# CAN-to-CAN.net
KiCad netlist of a schematic drawn in Altium Designer
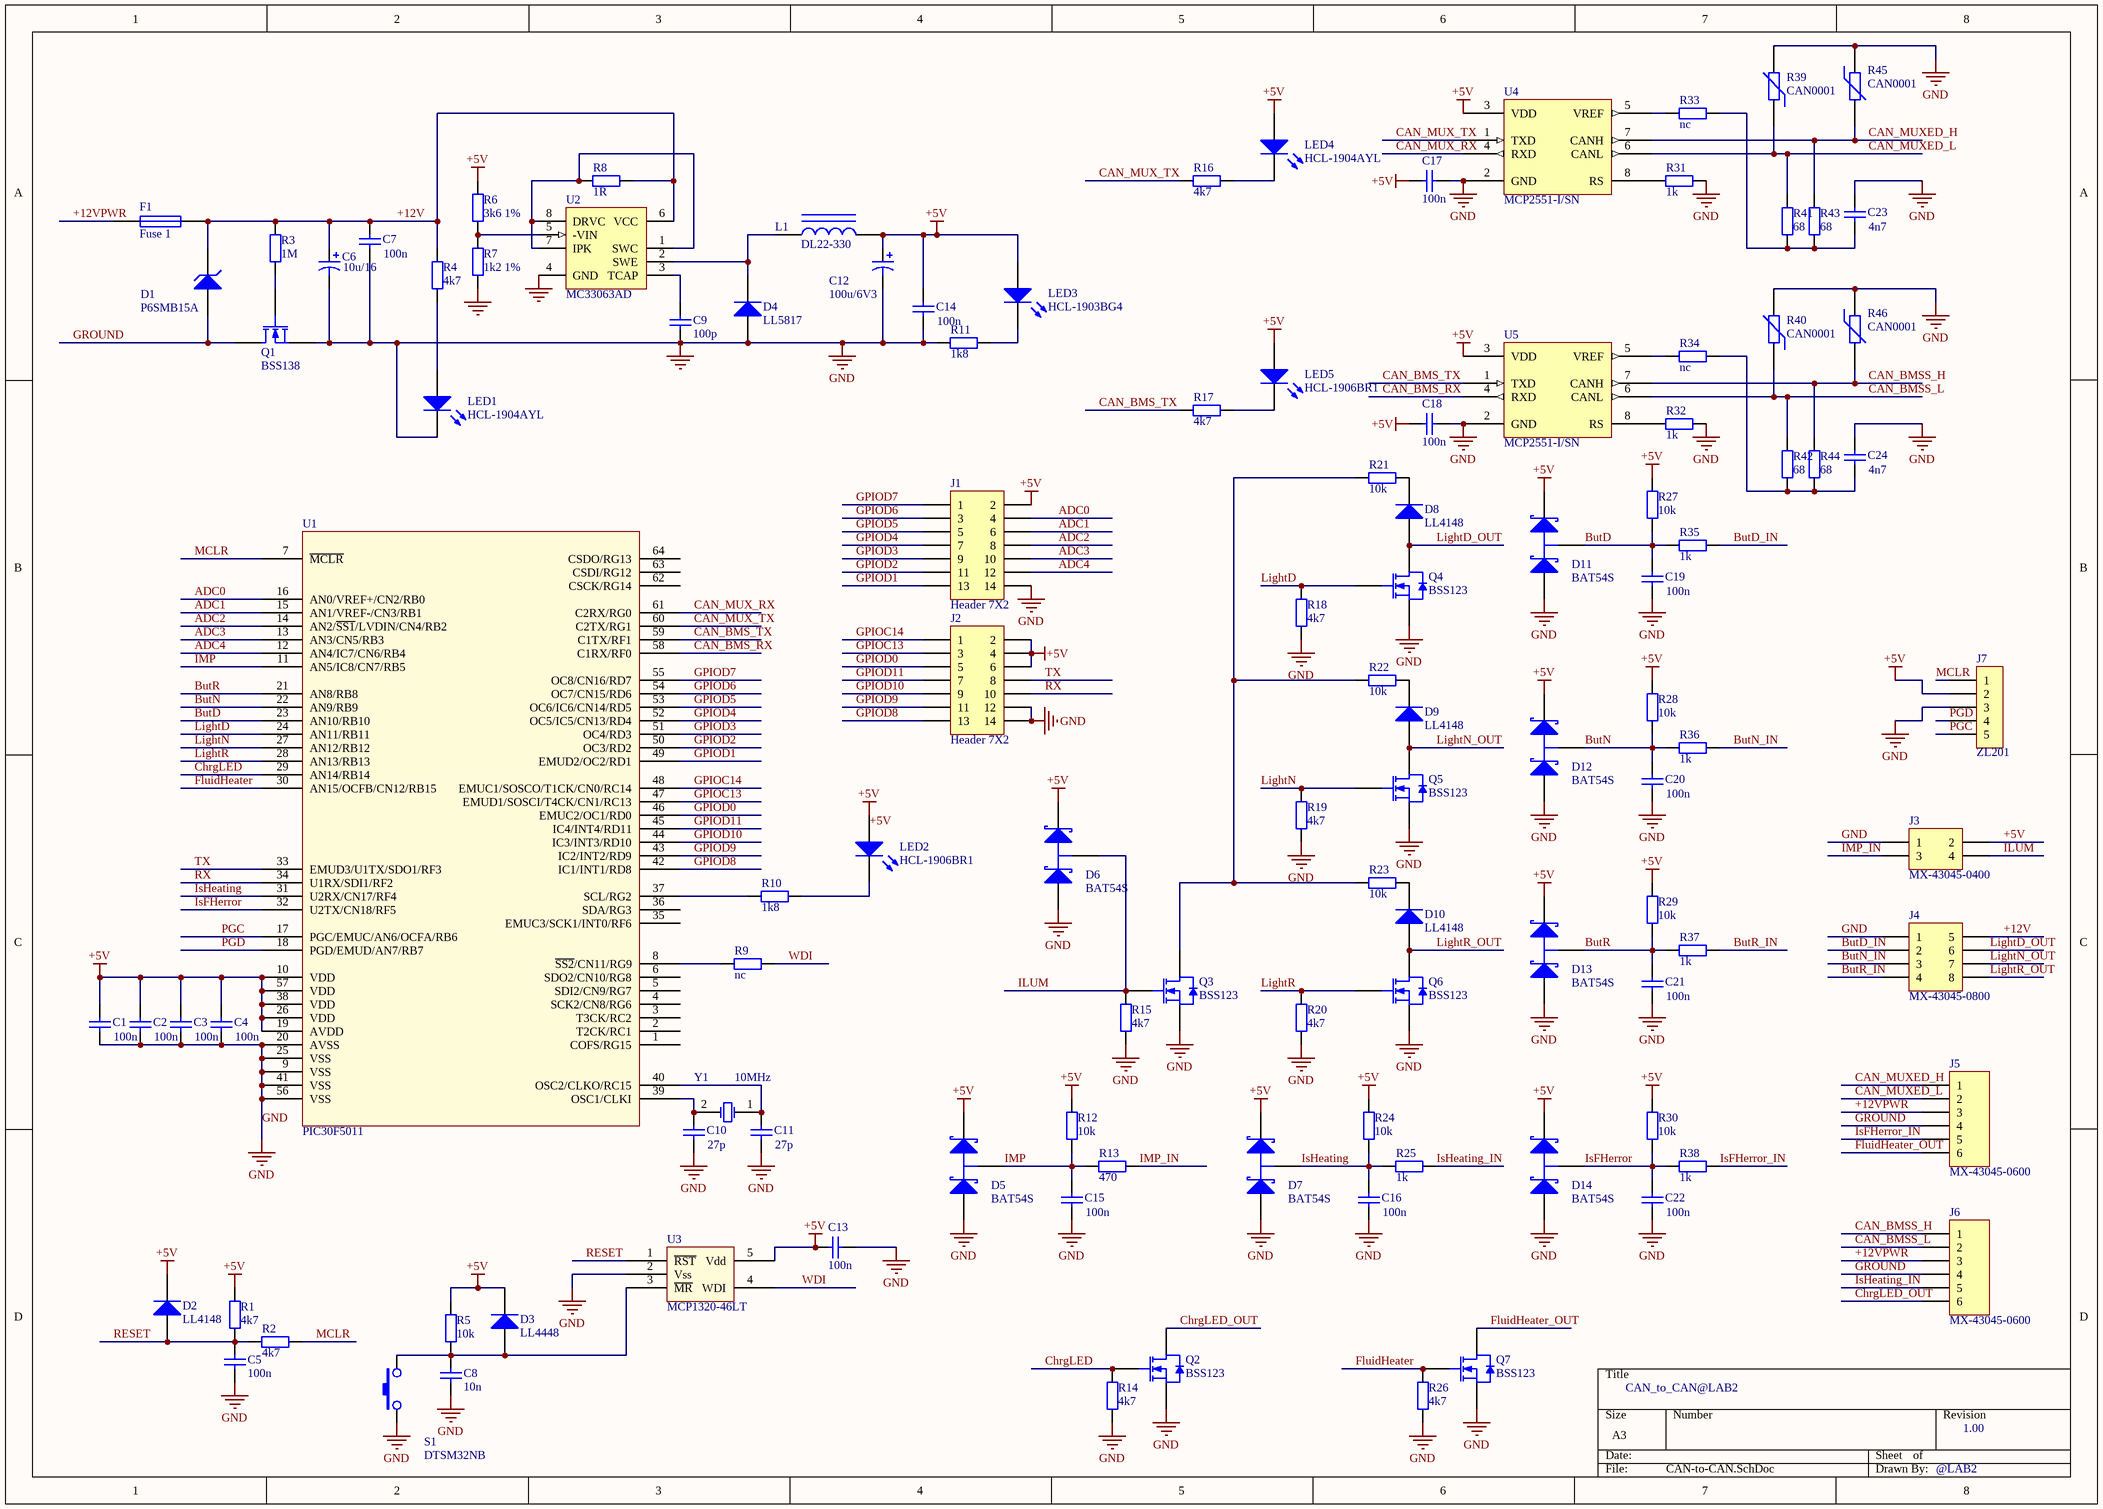
[diagram p0: CAN-to-CAN.SchDoc]

(export (version "E")
  (design (tool "Eeschema 10.0.6"))
  (components
    (comp (ref "C1")
      (value "100n")
      (footprint "0603")
      (description "Capacitor")
      (libsource (lib "Miscellaneous Devices") (part "Cap"))
    )
    (comp (ref "C2")
      (value "100n")
      (footprint "0603")
      (description "Capacitor")
      (libsource (lib "Miscellaneous Devices") (part "Cap"))
    )
    (comp (ref "C3")
      (value "100n")
      (footprint "0603")
      (description "Capacitor")
      (libsource (lib "Miscellaneous Devices") (part "Cap"))
    )
    (comp (ref "C4")
      (value "100n")
      (footprint "0603")
      (description "Capacitor")
      (libsource (lib "Miscellaneous Devices") (part "Cap"))
    )
    (comp (ref "C5")
      (value "100n")
      (footprint "0603")
      (description "Capacitor")
      (libsource (lib "Miscellaneous Devices") (part "Cap"))
    )
    (comp (ref "C6")
      (value "10u/16")
      (footprint "1608[0603]")
      (description "Polarized Capacitor (Radial)")
      (libsource (lib "Miscellaneous Devices") (part "Cap Pol1"))
    )
    (comp (ref "C7")
      (value "100n")
      (footprint "1812")
      (description "Capacitor")
      (libsource (lib "Miscellaneous Devices") (part "Cap"))
    )
    (comp (ref "C8")
      (value "10n")
      (footprint "0603")
      (description "Capacitor")
      (libsource (lib "Miscellaneous Devices") (part "Cap"))
    )
    (comp (ref "C9")
      (value "100p")
      (footprint "0603")
      (description "Capacitor")
      (libsource (lib "Miscellaneous Devices") (part "Cap"))
    )
    (comp (ref "C10")
      (value "27p")
      (footprint "0603")
      (description "Capacitor")
      (libsource (lib "Miscellaneous Devices") (part "Cap"))
    )
    (comp (ref "C11")
      (value "27p")
      (footprint "0603")
      (description "Capacitor")
      (libsource (lib "Miscellaneous Devices") (part "Cap"))
    )
    (comp (ref "C12")
      (value "100u/6V3")
      (footprint "0402")
      (description "Polarized Capacitor (Radial)")
      (libsource (lib "Miscellaneous Devices") (part "Cap Pol1"))
    )
    (comp (ref "C13")
      (value "100n")
      (footprint "0603")
      (description "Capacitor")
      (libsource (lib "Miscellaneous Devices") (part "Cap"))
    )
    (comp (ref "C14")
      (value "100n")
      (footprint "0603")
      (description "Capacitor")
      (libsource (lib "Miscellaneous Devices") (part "Cap"))
    )
    (comp (ref "C15")
      (value "100n")
      (footprint "0603")
      (description "Capacitor")
      (libsource (lib "Miscellaneous Devices") (part "Cap"))
    )
    (comp (ref "C16")
      (value "100n")
      (footprint "0603")
      (description "Capacitor")
      (libsource (lib "Miscellaneous Devices") (part "Cap"))
    )
    (comp (ref "C17")
      (value "100n")
      (footprint "0603")
      (description "Capacitor")
      (libsource (lib "Miscellaneous Devices") (part "Cap"))
    )
    (comp (ref "C18")
      (value "100n")
      (footprint "0603")
      (description "Capacitor")
      (libsource (lib "Miscellaneous Devices") (part "Cap"))
    )
    (comp (ref "C19")
      (value "100n")
      (footprint "0603")
      (description "Capacitor")
      (libsource (lib "Miscellaneous Devices") (part "Cap"))
    )
    (comp (ref "C20")
      (value "100n")
      (footprint "0603")
      (description "Capacitor")
      (libsource (lib "Miscellaneous Devices") (part "Cap"))
    )
    (comp (ref "C21")
      (value "100n")
      (footprint "0603")
      (description "Capacitor")
      (libsource (lib "Miscellaneous Devices") (part "Cap"))
    )
    (comp (ref "C22")
      (value "100n")
      (footprint "0603")
      (description "Capacitor")
      (libsource (lib "Miscellaneous Devices") (part "Cap"))
    )
    (comp (ref "C23")
      (value "4n7")
      (footprint "0603")
      (description "Capacitor")
      (libsource (lib "Miscellaneous Devices") (part "Cap"))
    )
    (comp (ref "C24")
      (value "4n7")
      (footprint "0603")
      (description "Capacitor")
      (libsource (lib "Miscellaneous Devices") (part "Cap"))
    )
    (comp (ref "D1")
      (value "P6SMB15A")
      (footprint "SMB")
      (description "Zener Diode")
      (libsource (lib "Miscellaneous Devices") (part "D Zener"))
    )
    (comp (ref "D2")
      (value "LL4148")
      (footprint "DIODE-0.4")
      (description "High Conductance Fast Diode")
      (libsource (lib "FSC Discrete Diode") (part "1N4148"))
    )
    (comp (ref "D3")
      (value "LL4448")
      (footprint "DIODE_SMC")
      (description "Default Diode")
      (libsource (lib "Miscellaneous Devices") (part "Diode"))
    )
    (comp (ref "D4")
      (value "LL5817")
      (footprint "DIODE-0.7")
      (description "High Conductance Fast Diode")
      (libsource (lib "FSC Discrete Diode") (part "1N4148"))
    )
    (comp (ref "D5")
      (value "BAT54S")
      (footprint "DO-35")
      (description "Schottky Barrier Double Diode")
      (libsource (lib "Philips Discrete Diode - Schottky") (part "BAT54S"))
    )
    (comp (ref "D6")
      (value "BAT54S")
      (footprint "DO-41")
      (description "Schottky Barrier Double Diode")
      (libsource (lib "Philips Discrete Diode - Schottky") (part "BAT54S"))
    )
    (comp (ref "D7")
      (value "BAT54S")
      (footprint "DO-204AL")
      (description "Schottky Barrier Double Diode")
      (libsource (lib "Philips Discrete Diode - Schottky") (part "BAT54S"))
    )
    (comp (ref "D8")
      (value "LL4148")
      (footprint "DO-201AD")
      (description "High Conductance Fast Diode")
      (libsource (lib "FSC Discrete Diode") (part "1N4148"))
    )
    (comp (ref "D9")
      (value "LL4148")
      (footprint "DIODE-0.4")
      (description "High Conductance Fast Diode")
      (libsource (lib "FSC Discrete Diode") (part "1N4148"))
    )
    (comp (ref "D10")
      (value "LL4148")
      (footprint "DO-7")
      (description "High Conductance Fast Diode")
      (libsource (lib "FSC Discrete Diode") (part "1N4148"))
    )
    (comp (ref "D11")
      (value "BAT54S")
      (footprint "DO-41")
      (description "Schottky Barrier Double Diode")
      (libsource (lib "Philips Discrete Diode - Schottky") (part "BAT54S"))
    )
    (comp (ref "D12")
      (value "BAT54S")
      (footprint "DO-201AD")
      (description "Schottky Barrier Double Diode")
      (libsource (lib "Philips Discrete Diode - Schottky") (part "BAT54S"))
    )
    (comp (ref "D13")
      (value "BAT54S")
      (footprint "DO-201AD")
      (description "Schottky Barrier Double Diode")
      (libsource (lib "Philips Discrete Diode - Schottky") (part "BAT54S"))
    )
    (comp (ref "D14")
      (value "BAT54S")
      (footprint "DO-41")
      (description "Schottky Barrier Double Diode")
      (libsource (lib "Philips Discrete Diode - Schottky") (part "BAT54S"))
    )
    (comp (ref "F1")
      (value "Fuse 1")
      (footprint "1812")
      (description "Fuse")
      (libsource (lib "Miscellaneous Devices") (part "Fuse 1"))
    )
    (comp (ref "J1")
      (value "Header 7X2")
      (footprint "HDR2X7")
      (description "Header, 7-Pin, Dual row")
      (libsource (lib "Miscellaneous Connectors") (part "Header 7X2"))
    )
    (comp (ref "J2")
      (value "Header 7X2")
      (footprint "HDR2X7")
      (description "Header, 7-Pin, Dual row")
      (libsource (lib "Miscellaneous Connectors") (part "Header 7X2"))
    )
    (comp (ref "J3")
      (value "MX-43045-0400")
      (footprint "SOT223_N")
      (description "Header, 2-Pin, Dual row")
      (libsource (lib "Miscellaneous Connectors") (part "Header 2X2"))
    )
    (comp (ref "J4")
      (value "MX-43045-0800")
      (footprint "DIP-8")
      (description "Header, 4-Pin, Dual row")
      (libsource (lib "Miscellaneous Connectors") (part "Header 4X2A"))
    )
    (comp (ref "J5")
      (value "MX-43045-0600")
      (footprint "DPDT-6")
      (description "Header, 6-Pin")
      (libsource (lib "Miscellaneous Connectors") (part "Header 6"))
    )
    (comp (ref "J6")
      (value "MX-43045-0600")
      (footprint "DPDT-6")
      (description "Header, 6-Pin")
      (libsource (lib "Miscellaneous Connectors") (part "Header 6"))
    )
    (comp (ref "J7")
      (value "ZL201")
      (footprint "HDR1X5")
      (description "Connector")
      (libsource (lib "*") (part "CON5"))
    )
    (comp (ref "L1")
      (value "DL22-330")
      (footprint "0603")
      (description "Magnetic-Core Inductor")
      (libsource (lib "Miscellaneous Devices") (part "Inductor Iron"))
    )
    (comp (ref "LED1")
      (value "HCL-1904AYL")
      (footprint "0603")
      (description "Typical BLUE SiC LED")
      (libsource (lib "Miscellaneous Devices") (part "LED3"))
    )
    (comp (ref "LED2")
      (value "HCL-1906BR1")
      (footprint "0603")
      (description "Typical BLUE SiC LED")
      (libsource (lib "Miscellaneous Devices") (part "LED3"))
    )
    (comp (ref "LED3")
      (value "HCL-1903BG4")
      (footprint "0603")
      (description "Typical BLUE SiC LED")
      (libsource (lib "Miscellaneous Devices") (part "LED3"))
    )
    (comp (ref "LED4")
      (value "HCL-1904AYL")
      (footprint "0603")
      (description "Typical BLUE SiC LED")
      (libsource (lib "Miscellaneous Devices") (part "LED3"))
    )
    (comp (ref "LED5")
      (value "HCL-1906BR1")
      (footprint "0603")
      (description "Typical BLUE SiC LED")
      (libsource (lib "Miscellaneous Devices") (part "LED3"))
    )
    (comp (ref "Q1")
      (value "BSS138")
      (footprint "SOT89L")
      (description "N-Channel Enhancement Mode Vertical DMOS FET")
      (libsource (lib "Zetex Discrete MOSFET") (part "BSS138"))
    )
    (comp (ref "Q2")
      (value "BSS123")
      (footprint "SOT23_M")
      (description "N-channel Enhancement Mode Vertical D-MOSFET")
      (libsource (lib "Philips Discrete MOSFET - Low Power") (part "BSS123"))
    )
    (comp (ref "Q3")
      (value "BSS123")
      (footprint "SOT23_M")
      (description "N-channel Enhancement Mode Vertical D-MOSFET")
      (libsource (lib "Philips Discrete MOSFET - Low Power") (part "BSS123"))
    )
    (comp (ref "Q4")
      (value "BSS123")
      (footprint "SOT89L")
      (description "N-channel Enhancement Mode Vertical D-MOSFET")
      (libsource (lib "Philips Discrete MOSFET - Low Power") (part "BSS123"))
    )
    (comp (ref "Q5")
      (value "BSS123")
      (footprint "DIP-P8")
      (description "N-channel Enhancement Mode Vertical D-MOSFET")
      (libsource (lib "Philips Discrete MOSFET - Low Power") (part "BSS123"))
    )
    (comp (ref "Q6")
      (value "BSS123")
      (footprint "DIODE_SMC")
      (description "N-channel Enhancement Mode Vertical D-MOSFET")
      (libsource (lib "Philips Discrete MOSFET - Low Power") (part "BSS123"))
    )
    (comp (ref "Q7")
      (value "BSS123")
      (footprint "SOT89N")
      (description "N-channel Enhancement Mode Vertical D-MOSFET")
      (libsource (lib "Philips Discrete MOSFET - Low Power") (part "BSS123"))
    )
    (comp (ref "R1")
      (value "4k7")
      (footprint "0603")
      (description "Resistor")
      (libsource (lib "") (part "Res2_2"))
    )
    (comp (ref "R2")
      (value "4k7")
      (footprint "0603")
      (description "Resistor")
      (libsource (lib "Miscellaneous Devices") (part "Res2"))
    )
    (comp (ref "R3")
      (value "1M")
      (footprint "6-0805_L")
      (description "Resistor")
      (libsource (lib "") (part "Res2_2"))
    )
    (comp (ref "R4")
      (value "4k7")
      (footprint "6-0805_N")
      (description "Resistor")
      (libsource (lib "") (part "Res2_2"))
    )
    (comp (ref "R5")
      (value "10k")
      (footprint "0603")
      (description "Resistor")
      (libsource (lib "") (part "Res2_3"))
    )
    (comp (ref "R6")
      (value "3k6 1%")
      (footprint "0603")
      (description "Resistor")
      (libsource (lib "") (part "Res2_2"))
    )
    (comp (ref "R7")
      (value "1k2 1%")
      (footprint "0603")
      (description "Resistor")
      (libsource (lib "") (part "Res2_3"))
    )
    (comp (ref "R8")
      (value "1R")
      (footprint "6-0805_L")
      (description "Resistor")
      (libsource (lib "") (part "Res2_1"))
    )
    (comp (ref "R9")
      (value "nc")
      (footprint "0603")
      (description "Resistor")
      (libsource (lib "Miscellaneous Devices") (part "Res2"))
    )
    (comp (ref "R10")
      (value "1k8")
      (footprint "0603")
      (description "Resistor")
      (libsource (lib "Miscellaneous Devices") (part "Res2"))
    )
    (comp (ref "R11")
      (value "1k8")
      (footprint "0603")
      (description "Resistor")
      (libsource (lib "Miscellaneous Devices") (part "Res2"))
    )
    (comp (ref "R12")
      (value "10k")
      (footprint "0603")
      (description "Resistor")
      (libsource (lib "") (part "Res2_2"))
    )
    (comp (ref "R13")
      (value "470")
      (footprint "0603")
      (description "Resistor")
      (libsource (lib "Miscellaneous Devices") (part "Res2"))
    )
    (comp (ref "R14")
      (value "4k7")
      (footprint "0603")
      (description "Resistor")
      (libsource (lib "") (part "Res2_2"))
    )
    (comp (ref "R15")
      (value "4k7")
      (footprint "0603")
      (description "Resistor")
      (libsource (lib "") (part "Res2_2"))
    )
    (comp (ref "R16")
      (value "4k7")
      (footprint "0603")
      (description "Resistor")
      (libsource (lib "Miscellaneous Devices") (part "Res2"))
    )
    (comp (ref "R17")
      (value "4k7")
      (footprint "0603")
      (description "Resistor")
      (libsource (lib "Miscellaneous Devices") (part "Res2"))
    )
    (comp (ref "R18")
      (value "4k7")
      (footprint "0603")
      (description "Resistor")
      (libsource (lib "") (part "Res2_2"))
    )
    (comp (ref "R19")
      (value "4k7")
      (footprint "0603")
      (description "Resistor")
      (libsource (lib "") (part "Res2_2"))
    )
    (comp (ref "R20")
      (value "4k7")
      (footprint "0603")
      (description "Resistor")
      (libsource (lib "") (part "Res2_2"))
    )
    (comp (ref "R21")
      (value "10k")
      (footprint "0603")
      (description "Resistor")
      (libsource (lib "") (part "Res2_1"))
    )
    (comp (ref "R22")
      (value "10k")
      (footprint "0603")
      (description "Resistor")
      (libsource (lib "") (part "Res2_1"))
    )
    (comp (ref "R23")
      (value "10k")
      (footprint "0603")
      (description "Resistor")
      (libsource (lib "") (part "Res2_1"))
    )
    (comp (ref "R24")
      (value "10k")
      (footprint "0603")
      (description "Resistor")
      (libsource (lib "") (part "Res2_2"))
    )
    (comp (ref "R25")
      (value "1k")
      (footprint "0603")
      (description "Resistor")
      (libsource (lib "Miscellaneous Devices") (part "Res2"))
    )
    (comp (ref "R26")
      (value "4k7")
      (footprint "0603")
      (description "Resistor")
      (libsource (lib "") (part "Res2_2"))
    )
    (comp (ref "R27")
      (value "10k")
      (footprint "0603")
      (description "Resistor")
      (libsource (lib "") (part "Res2_2"))
    )
    (comp (ref "R28")
      (value "10k")
      (footprint "0603")
      (description "Resistor")
      (libsource (lib "") (part "Res2_2"))
    )
    (comp (ref "R29")
      (value "10k")
      (footprint "0603")
      (description "Resistor")
      (libsource (lib "") (part "Res2_2"))
    )
    (comp (ref "R30")
      (value "10k")
      (footprint "0603")
      (description "Resistor")
      (libsource (lib "") (part "Res2_2"))
    )
    (comp (ref "R31")
      (value "1k")
      (footprint "0603")
      (description "Resistor")
      (libsource (lib "") (part "Res2_1"))
    )
    (comp (ref "R32")
      (value "1k")
      (footprint "0603")
      (description "Resistor")
      (libsource (lib "") (part "Res2_1"))
    )
    (comp (ref "R33")
      (value "nc")
      (footprint "0603")
      (description "Resistor")
      (libsource (lib "") (part "Res2_1"))
    )
    (comp (ref "R34")
      (value "nc")
      (footprint "0603")
      (description "Resistor")
      (libsource (lib "") (part "Res2_1"))
    )
    (comp (ref "R35")
      (value "1k")
      (footprint "0603")
      (description "Resistor")
      (libsource (lib "Miscellaneous Devices") (part "Res2"))
    )
    (comp (ref "R36")
      (value "1k")
      (footprint "0603")
      (description "Resistor")
      (libsource (lib "Miscellaneous Devices") (part "Res2"))
    )
    (comp (ref "R37")
      (value "1k")
      (footprint "0603")
      (description "Resistor")
      (libsource (lib "Miscellaneous Devices") (part "Res2"))
    )
    (comp (ref "R38")
      (value "1k")
      (footprint "0603")
      (description "Resistor")
      (libsource (lib "Miscellaneous Devices") (part "Res2"))
    )
    (comp (ref "R39")
      (value "CAN0001")
      (footprint "0603")
      (description "Varistor (Voltage-Sensitive Resistor)")
      (libsource (lib "Miscellaneous Devices") (part "Res Varistor"))
    )
    (comp (ref "R40")
      (value "CAN0001")
      (footprint "0603")
      (description "Varistor (Voltage-Sensitive Resistor)")
      (libsource (lib "Miscellaneous Devices") (part "Res Varistor"))
    )
    (comp (ref "R41")
      (value "68")
      (footprint "0603")
      (description "Resistor")
      (libsource (lib "") (part "Res2_2"))
    )
    (comp (ref "R42")
      (value "68")
      (footprint "0603")
      (description "Resistor")
      (libsource (lib "") (part "Res2_2"))
    )
    (comp (ref "R43")
      (value "68")
      (footprint "0603")
      (description "Resistor")
      (libsource (lib "") (part "Res2_2"))
    )
    (comp (ref "R44")
      (value "68")
      (footprint "0603")
      (description "Resistor")
      (libsource (lib "") (part "Res2_2"))
    )
    (comp (ref "R45")
      (value "CAN0001")
      (footprint "0603")
      (description "Varistor (Voltage-Sensitive Resistor)")
      (libsource (lib "Miscellaneous Devices") (part "Res Varistor"))
    )
    (comp (ref "R46")
      (value "CAN0001")
      (footprint "0603")
      (description "Varistor (Voltage-Sensitive Resistor)")
      (libsource (lib "Miscellaneous Devices") (part "Res Varistor"))
    )
    (comp (ref "S1")
      (value "DTSM32NB")
      (footprint "PIN-W2/E2.8")
      (description "Switch PushButton")
      (libsource (lib "*") (part "PUSHB"))
    )
    (comp (ref "U1")
      (value "PIC30F5011")
      (footprint "TQFP-64_L")
      (description "PIC30F5011 - Up")
      (libsource (lib "AD Microcontroller ARM") (part "PIC30F5011"))
    )
    (comp (ref "U2")
      (value "MC33063AD")
      (footprint "SO8_N")
      (description "DC-to-DC Converter Control Circuit")
      (libsource (lib "Motorola Power Mgt DC-DC Converter") (part "MC33063AD"))
    )
    (comp (ref "U3")
      (value "MCP1320-46LT")
      (footprint "MODULE5B")
      (libsource (lib "X-Tro's Misc") (part "MCP1320"))
    )
    (comp (ref "U4")
      (value "MCP2551-I/SN")
      (footprint "DB008_L")
      (description "High Speed CAN Transceiver, 8-Pin Plastic SOIC, Industrial Grade")
      (libsource (lib "Microchip Interface Line Transceiver") (part "MCP2551-I/SN"))
    )
    (comp (ref "U5")
      (value "MCP2551-I/SN")
      (footprint "DIP-8")
      (description "High Speed CAN Transceiver, 8-Pin Plastic SOIC, Industrial Grade")
      (libsource (lib "Microchip Interface Line Transceiver") (part "MCP2551-I/SN"))
    )
    (comp (ref "Y1")
      (value "10MHz")
      (footprint "SPST-2")
      (description "Crystal Oscillator")
      (libsource (lib "Miscellaneous Devices") (part "XTAL"))
    )
  )
  (nets
    (net (code "1") (name "+5V") (class "Default")
      (node (ref "C1") (pin "1") (pinfunction "1_1") (pintype "passive"))
      (node (ref "C12") (pin "1") (pinfunction "1_1") (pintype "passive"))
      (node (ref "C13") (pin "1") (pinfunction "1_1") (pintype "passive"))
      (node (ref "C14") (pin "1") (pinfunction "1_1") (pintype "passive"))
      (node (ref "C17") (pin "1") (pinfunction "1_1") (pintype "passive"))
      (node (ref "C18") (pin "1") (pinfunction "1_1") (pintype "passive"))
      (node (ref "C2") (pin "1") (pinfunction "1_1") (pintype "passive"))
      (node (ref "C3") (pin "1") (pinfunction "1_1") (pintype "passive"))
      (node (ref "C4") (pin "1") (pinfunction "1_1") (pintype "passive"))
      (node (ref "D11") (pin "2") (pinfunction "K_2") (pintype "passive"))
      (node (ref "D12") (pin "2") (pinfunction "K_2") (pintype "passive"))
      (node (ref "D13") (pin "2") (pinfunction "K_2") (pintype "passive"))
      (node (ref "D14") (pin "2") (pinfunction "K_2") (pintype "passive"))
      (node (ref "D2") (pin "2") (pinfunction "K_2") (pintype "passive"))
      (node (ref "D3") (pin "2") (pinfunction "K_2") (pintype "passive"))
      (node (ref "D5") (pin "2") (pinfunction "K_2") (pintype "passive"))
      (node (ref "D6") (pin "2") (pinfunction "K_2") (pintype "passive"))
      (node (ref "D7") (pin "2") (pinfunction "K_2") (pintype "passive"))
      (node (ref "J1") (pin "2") (pinfunction "2_2") (pintype "passive"))
      (node (ref "J2") (pin "2") (pinfunction "2_2") (pintype "passive"))
      (node (ref "J2") (pin "4") (pinfunction "4_4") (pintype "passive"))
      (node (ref "J2") (pin "6") (pinfunction "6_6") (pintype "passive"))
      (node (ref "J3") (pin "2") (pinfunction "2_2") (pintype "passive"))
      (node (ref "J7") (pin "2") (pinfunction "2_2") (pintype "passive"))
      (node (ref "L1") (pin "2") (pinfunction "2_2") (pintype "passive"))
      (node (ref "LED2") (pin "1") (pinfunction "A_1") (pintype "passive"))
      (node (ref "LED3") (pin "1") (pinfunction "A_1") (pintype "passive"))
      (node (ref "LED4") (pin "1") (pinfunction "A_1") (pintype "passive"))
      (node (ref "LED5") (pin "1") (pinfunction "A_1") (pintype "passive"))
      (node (ref "R1") (pin "1") (pinfunction "1_1") (pintype "passive"))
      (node (ref "R12") (pin "1") (pinfunction "1_1") (pintype "passive"))
      (node (ref "R24") (pin "1") (pinfunction "1_1") (pintype "passive"))
      (node (ref "R27") (pin "1") (pinfunction "1_1") (pintype "passive"))
      (node (ref "R28") (pin "1") (pinfunction "1_1") (pintype "passive"))
      (node (ref "R29") (pin "1") (pinfunction "1_1") (pintype "passive"))
      (node (ref "R30") (pin "1") (pinfunction "1_1") (pintype "passive"))
      (node (ref "R5") (pin "2") (pinfunction "2_2") (pintype "passive"))
      (node (ref "R6") (pin "1") (pinfunction "1_1") (pintype "passive"))
      (node (ref "U1") (pin "10") (pinfunction "VDD_10") (pintype "passive"))
      (node (ref "U1") (pin "19") (pinfunction "AVDD_19") (pintype "passive"))
      (node (ref "U1") (pin "26") (pinfunction "VDD_26") (pintype "passive"))
      (node (ref "U1") (pin "38") (pinfunction "VDD_38") (pintype "passive"))
      (node (ref "U1") (pin "57") (pinfunction "VDD_57") (pintype "passive"))
      (node (ref "U3") (pin "5") (pinfunction "Vdd_5") (pintype "passive"))
      (node (ref "U4") (pin "3") (pinfunction "VDD_3") (pintype "power_in"))
      (node (ref "U5") (pin "3") (pinfunction "VDD_3") (pintype "power_in"))
    )
    (net (code "2") (name "/+12V") (class "Default")
      (node (ref "C6") (pin "1") (pinfunction "1_1") (pintype "passive"))
      (node (ref "C7") (pin "1") (pinfunction "1_1") (pintype "passive"))
      (node (ref "D1") (pin "2") (pinfunction "K_2") (pintype "passive"))
      (node (ref "F1") (pin "2") (pinfunction "2_2") (pintype "passive"))
      (node (ref "J4") (pin "5") (pinfunction "5_5") (pintype "passive"))
      (node (ref "R3") (pin "1") (pinfunction "1_1") (pintype "passive"))
      (node (ref "R4") (pin "1") (pinfunction "1_1") (pintype "passive"))
      (node (ref "R8") (pin "2") (pinfunction "2_2") (pintype "passive"))
      (node (ref "U2") (pin "6") (pinfunction "VCC_6") (pintype "power_in"))
    )
    (net (code "3") (name "/+12VPWR") (class "Default")
      (node (ref "F1") (pin "1") (pinfunction "1_1") (pintype "passive"))
      (node (ref "J5") (pin "3") (pinfunction "3_3") (pintype "passive"))
      (node (ref "J6") (pin "3") (pinfunction "3_3") (pintype "passive"))
    )
    (net (code "4") (name "/ADC0") (class "Default")
      (node (ref "J1") (pin "4") (pinfunction "4_4") (pintype "passive"))
      (node (ref "U1") (pin "16") (pinfunction "AN0/VREF+/CN2/RB0_16") (pintype "passive"))
    )
    (net (code "5") (name "/ADC1") (class "Default")
      (node (ref "J1") (pin "6") (pinfunction "6_6") (pintype "passive"))
      (node (ref "U1") (pin "15") (pinfunction "AN1/VREF-/CN3/RB1_15") (pintype "passive"))
    )
    (net (code "6") (name "/ADC2") (class "Default")
      (node (ref "J1") (pin "8") (pinfunction "8_8") (pintype "passive"))
      (node (ref "U1") (pin "14") (pinfunction "AN2/~{SS1}/LVDIN/CN4/RB2_14") (pintype "passive"))
    )
    (net (code "7") (name "/ADC3") (class "Default")
      (node (ref "J1") (pin "10") (pinfunction "10_10") (pintype "passive"))
      (node (ref "U1") (pin "13") (pinfunction "AN3/CN5/RB3_13") (pintype "passive"))
    )
    (net (code "8") (name "/ADC4") (class "Default")
      (node (ref "J1") (pin "12") (pinfunction "12_12") (pintype "passive"))
      (node (ref "U1") (pin "12") (pinfunction "AN4/IC7/CN6/RB4_12") (pintype "passive"))
    )
    (net (code "9") (name "/ButD") (class "Default")
      (node (ref "C19") (pin "1") (pinfunction "1_1") (pintype "passive"))
      (node (ref "D11") (pin "3") (pinfunction "C_3") (pintype "passive"))
      (node (ref "R27") (pin "2") (pinfunction "2_2") (pintype "passive"))
      (node (ref "R35") (pin "2") (pinfunction "2_2") (pintype "passive"))
      (node (ref "U1") (pin "23") (pinfunction "AN10/RB10_23") (pintype "passive"))
    )
    (net (code "10") (name "/ButD_IN") (class "Default")
      (node (ref "J4") (pin "2") (pinfunction "2_2") (pintype "passive"))
      (node (ref "R35") (pin "1") (pinfunction "1_1") (pintype "passive"))
    )
    (net (code "11") (name "/ButN") (class "Default")
      (node (ref "C20") (pin "1") (pinfunction "1_1") (pintype "passive"))
      (node (ref "D12") (pin "3") (pinfunction "C_3") (pintype "passive"))
      (node (ref "R28") (pin "2") (pinfunction "2_2") (pintype "passive"))
      (node (ref "R36") (pin "2") (pinfunction "2_2") (pintype "passive"))
      (node (ref "U1") (pin "22") (pinfunction "AN9/RB9_22") (pintype "passive"))
    )
    (net (code "12") (name "/ButN_IN") (class "Default")
      (node (ref "J4") (pin "3") (pinfunction "3_3") (pintype "passive"))
      (node (ref "R36") (pin "1") (pinfunction "1_1") (pintype "passive"))
    )
    (net (code "13") (name "/ButR") (class "Default")
      (node (ref "C21") (pin "1") (pinfunction "1_1") (pintype "passive"))
      (node (ref "D13") (pin "3") (pinfunction "C_3") (pintype "passive"))
      (node (ref "R29") (pin "2") (pinfunction "2_2") (pintype "passive"))
      (node (ref "R37") (pin "2") (pinfunction "2_2") (pintype "passive"))
      (node (ref "U1") (pin "21") (pinfunction "AN8/RB8_21") (pintype "passive"))
    )
    (net (code "14") (name "/ButR_IN") (class "Default")
      (node (ref "J4") (pin "4") (pinfunction "4_4") (pintype "passive"))
      (node (ref "R37") (pin "1") (pinfunction "1_1") (pintype "passive"))
    )
    (net (code "15") (name "/CAN_BMSS_H") (class "Default")
      (node (ref "J6") (pin "1") (pinfunction "1_1") (pintype "passive"))
      (node (ref "R44") (pin "1") (pinfunction "1_1") (pintype "passive"))
      (node (ref "R46") (pin "2") (pinfunction "2_2") (pintype "passive"))
      (node (ref "U5") (pin "7") (pinfunction "CANH_7") (pintype "output"))
    )
    (net (code "16") (name "/CAN_BMSS_L") (class "Default")
      (node (ref "J6") (pin "2") (pinfunction "2_2") (pintype "passive"))
      (node (ref "R40") (pin "1") (pinfunction "1_1") (pintype "passive"))
      (node (ref "R42") (pin "1") (pinfunction "1_1") (pintype "passive"))
      (node (ref "U5") (pin "6") (pinfunction "CANL_6") (pintype "output"))
    )
    (net (code "17") (name "/CAN_BMS_RX") (class "Default")
      (node (ref "U1") (pin "58") (pinfunction "C1RX/RF0_58") (pintype "passive"))
      (node (ref "U5") (pin "4") (pinfunction "RXD_4") (pintype "output"))
    )
    (net (code "18") (name "/CAN_BMS_TX") (class "Default")
      (node (ref "R17") (pin "2") (pinfunction "2_2") (pintype "passive"))
      (node (ref "U1") (pin "59") (pinfunction "C1TX/RF1_59") (pintype "passive"))
      (node (ref "U5") (pin "1") (pinfunction "TXD_1") (pintype "input"))
    )
    (net (code "19") (name "/CAN_MUXED_H") (class "Default")
      (node (ref "J5") (pin "1") (pinfunction "1_1") (pintype "passive"))
      (node (ref "R43") (pin "1") (pinfunction "1_1") (pintype "passive"))
      (node (ref "R45") (pin "2") (pinfunction "2_2") (pintype "passive"))
      (node (ref "U4") (pin "7") (pinfunction "CANH_7") (pintype "output"))
    )
    (net (code "20") (name "/CAN_MUXED_L") (class "Default")
      (node (ref "J5") (pin "2") (pinfunction "2_2") (pintype "passive"))
      (node (ref "R39") (pin "1") (pinfunction "1_1") (pintype "passive"))
      (node (ref "R41") (pin "1") (pinfunction "1_1") (pintype "passive"))
      (node (ref "U4") (pin "6") (pinfunction "CANL_6") (pintype "output"))
    )
    (net (code "21") (name "/CAN_MUX_RX") (class "Default")
      (node (ref "U1") (pin "61") (pinfunction "C2RX/RG0_61") (pintype "passive"))
      (node (ref "U4") (pin "4") (pinfunction "RXD_4") (pintype "output"))
    )
    (net (code "22") (name "/CAN_MUX_TX") (class "Default")
      (node (ref "R16") (pin "2") (pinfunction "2_2") (pintype "passive"))
      (node (ref "U1") (pin "60") (pinfunction "C2TX/RG1_60") (pintype "passive"))
      (node (ref "U4") (pin "1") (pinfunction "TXD_1") (pintype "input"))
    )
    (net (code "23") (name "/ChrgLED") (class "Default")
      (node (ref "Q2") (pin "3") (pinfunction "G_3") (pintype "passive"))
      (node (ref "R14") (pin "1") (pinfunction "1_1") (pintype "passive"))
      (node (ref "U1") (pin "29") (pinfunction "AN14/RB14_29") (pintype "passive"))
    )
    (net (code "24") (name "/ChrgLED_OUT") (class "Default")
      (node (ref "J6") (pin "6") (pinfunction "6_6") (pintype "passive"))
      (node (ref "Q2") (pin "1") (pinfunction "D_1") (pintype "passive"))
    )
    (net (code "25") (name "/FluidHeater") (class "Default")
      (node (ref "Q7") (pin "3") (pinfunction "G_3") (pintype "passive"))
      (node (ref "R26") (pin "1") (pinfunction "1_1") (pintype "passive"))
      (node (ref "U1") (pin "30") (pinfunction "AN15/OCFB/CN12/RB15_30") (pintype "passive"))
    )
    (net (code "26") (name "/FluidHeater_OUT") (class "Default")
      (node (ref "J5") (pin "6") (pinfunction "6_6") (pintype "passive"))
      (node (ref "Q7") (pin "1") (pinfunction "D_1") (pintype "passive"))
    )
    (net (code "27") (name "/GPIOC13") (class "Default")
      (node (ref "J2") (pin "3") (pinfunction "3_3") (pintype "passive"))
      (node (ref "U1") (pin "47") (pinfunction "EMUD1/SOSCI/T4CK/CN1/RC13_47") (pintype "passive"))
    )
    (net (code "28") (name "/GPIOC14") (class "Default")
      (node (ref "J2") (pin "1") (pinfunction "1_1") (pintype "passive"))
      (node (ref "U1") (pin "48") (pinfunction "EMUC1/SOSCO/T1CK/CN0/RC14_48") (pintype "passive"))
    )
    (net (code "29") (name "/GPIOD0") (class "Default")
      (node (ref "J2") (pin "5") (pinfunction "5_5") (pintype "passive"))
      (node (ref "U1") (pin "46") (pinfunction "EMUC2/OC1/RD0_46") (pintype "passive"))
    )
    (net (code "30") (name "/GPIOD1") (class "Default")
      (node (ref "J1") (pin "13") (pinfunction "13_13") (pintype "passive"))
      (node (ref "U1") (pin "49") (pinfunction "EMUD2/OC2/RD1_49") (pintype "passive"))
    )
    (net (code "31") (name "/GPIOD2") (class "Default")
      (node (ref "J1") (pin "11") (pinfunction "11_11") (pintype "passive"))
      (node (ref "U1") (pin "50") (pinfunction "OC3/RD2_50") (pintype "passive"))
    )
    (net (code "32") (name "/GPIOD3") (class "Default")
      (node (ref "J1") (pin "9") (pinfunction "9_9") (pintype "passive"))
      (node (ref "U1") (pin "51") (pinfunction "OC4/RD3_51") (pintype "passive"))
    )
    (net (code "33") (name "/GPIOD4") (class "Default")
      (node (ref "J1") (pin "7") (pinfunction "7_7") (pintype "passive"))
      (node (ref "U1") (pin "52") (pinfunction "OC5/IC5/CN13/RD4_52") (pintype "passive"))
    )
    (net (code "34") (name "/GPIOD5") (class "Default")
      (node (ref "J1") (pin "5") (pinfunction "5_5") (pintype "passive"))
      (node (ref "U1") (pin "53") (pinfunction "OC6/IC6/CN14/RD5_53") (pintype "passive"))
    )
    (net (code "35") (name "/GPIOD6") (class "Default")
      (node (ref "J1") (pin "3") (pinfunction "3_3") (pintype "passive"))
      (node (ref "U1") (pin "54") (pinfunction "OC7/CN15/RD6_54") (pintype "passive"))
    )
    (net (code "36") (name "/GPIOD7") (class "Default")
      (node (ref "J1") (pin "1") (pinfunction "1_1") (pintype "passive"))
      (node (ref "U1") (pin "55") (pinfunction "OC8/CN16/RD7_55") (pintype "passive"))
    )
    (net (code "37") (name "/GPIOD8") (class "Default")
      (node (ref "J2") (pin "13") (pinfunction "13_13") (pintype "passive"))
      (node (ref "U1") (pin "42") (pinfunction "IC1/INT1/RD8_42") (pintype "passive"))
    )
    (net (code "38") (name "/GPIOD9") (class "Default")
      (node (ref "J2") (pin "11") (pinfunction "11_11") (pintype "passive"))
      (node (ref "U1") (pin "43") (pinfunction "IC2/INT2/RD9_43") (pintype "passive"))
    )
    (net (code "39") (name "/GPIOD10") (class "Default")
      (node (ref "J2") (pin "9") (pinfunction "9_9") (pintype "passive"))
      (node (ref "U1") (pin "44") (pinfunction "IC3/INT3/RD10_44") (pintype "passive"))
    )
    (net (code "40") (name "/GPIOD11") (class "Default")
      (node (ref "J2") (pin "7") (pinfunction "7_7") (pintype "passive"))
      (node (ref "U1") (pin "45") (pinfunction "IC4/INT4/RD11_45") (pintype "passive"))
    )
    (net (code "41") (name "/GROUND") (class "Default")
      (node (ref "D1") (pin "1") (pinfunction "A_1") (pintype "passive"))
      (node (ref "J5") (pin "4") (pinfunction "4_4") (pintype "passive"))
      (node (ref "J6") (pin "4") (pinfunction "4_4") (pintype "passive"))
      (node (ref "Q1") (pin "1") (pinfunction "D_1") (pintype "passive"))
    )
    (net (code "42") (name "/ILUM") (class "Default")
      (node (ref "D6") (pin "3") (pinfunction "C_3") (pintype "passive"))
      (node (ref "J3") (pin "4") (pinfunction "4_4") (pintype "passive"))
      (node (ref "Q3") (pin "3") (pinfunction "G_3") (pintype "passive"))
      (node (ref "R15") (pin "1") (pinfunction "1_1") (pintype "passive"))
    )
    (net (code "43") (name "/IMP") (class "Default")
      (node (ref "C15") (pin "1") (pinfunction "1_1") (pintype "passive"))
      (node (ref "D5") (pin "3") (pinfunction "C_3") (pintype "passive"))
      (node (ref "R12") (pin "2") (pinfunction "2_2") (pintype "passive"))
      (node (ref "R13") (pin "2") (pinfunction "2_2") (pintype "passive"))
      (node (ref "U1") (pin "11") (pinfunction "AN5/IC8/CN7/RB5_11") (pintype "passive"))
    )
    (net (code "44") (name "/IMP_IN") (class "Default")
      (node (ref "J3") (pin "3") (pinfunction "3_3") (pintype "passive"))
      (node (ref "R13") (pin "1") (pinfunction "1_1") (pintype "passive"))
    )
    (net (code "45") (name "/IsFHerror") (class "Default")
      (node (ref "C22") (pin "1") (pinfunction "1_1") (pintype "passive"))
      (node (ref "D14") (pin "3") (pinfunction "C_3") (pintype "passive"))
      (node (ref "R30") (pin "2") (pinfunction "2_2") (pintype "passive"))
      (node (ref "R38") (pin "2") (pinfunction "2_2") (pintype "passive"))
      (node (ref "U1") (pin "32") (pinfunction "U2TX/CN18/RF5_32") (pintype "passive"))
    )
    (net (code "46") (name "/IsFHerror_IN") (class "Default")
      (node (ref "J5") (pin "5") (pinfunction "5_5") (pintype "passive"))
      (node (ref "R38") (pin "1") (pinfunction "1_1") (pintype "passive"))
    )
    (net (code "47") (name "/IsHeating") (class "Default")
      (node (ref "C16") (pin "1") (pinfunction "1_1") (pintype "passive"))
      (node (ref "D7") (pin "3") (pinfunction "C_3") (pintype "passive"))
      (node (ref "R24") (pin "2") (pinfunction "2_2") (pintype "passive"))
      (node (ref "R25") (pin "2") (pinfunction "2_2") (pintype "passive"))
      (node (ref "U1") (pin "31") (pinfunction "U2RX/CN17/RF4_31") (pintype "passive"))
    )
    (net (code "48") (name "/IsHeating_IN") (class "Default")
      (node (ref "J6") (pin "5") (pinfunction "5_5") (pintype "passive"))
      (node (ref "R25") (pin "1") (pinfunction "1_1") (pintype "passive"))
    )
    (net (code "49") (name "/LightD") (class "Default")
      (node (ref "Q4") (pin "3") (pinfunction "G_3") (pintype "passive"))
      (node (ref "R18") (pin "1") (pinfunction "1_1") (pintype "passive"))
      (node (ref "U1") (pin "24") (pinfunction "AN11/RB11_24") (pintype "passive"))
    )
    (net (code "50") (name "/LightD_OUT") (class "Default")
      (node (ref "D8") (pin "1") (pinfunction "A_1") (pintype "passive"))
      (node (ref "J4") (pin "6") (pinfunction "6_6") (pintype "passive"))
      (node (ref "Q4") (pin "1") (pinfunction "D_1") (pintype "passive"))
    )
    (net (code "51") (name "/LightN") (class "Default")
      (node (ref "Q5") (pin "3") (pinfunction "G_3") (pintype "passive"))
      (node (ref "R19") (pin "1") (pinfunction "1_1") (pintype "passive"))
      (node (ref "U1") (pin "27") (pinfunction "AN12/RB12_27") (pintype "passive"))
    )
    (net (code "52") (name "/LightN_OUT") (class "Default")
      (node (ref "D9") (pin "1") (pinfunction "A_1") (pintype "passive"))
      (node (ref "J4") (pin "7") (pinfunction "7_7") (pintype "passive"))
      (node (ref "Q5") (pin "1") (pinfunction "D_1") (pintype "passive"))
    )
    (net (code "53") (name "/LightR") (class "Default")
      (node (ref "Q6") (pin "3") (pinfunction "G_3") (pintype "passive"))
      (node (ref "R20") (pin "1") (pinfunction "1_1") (pintype "passive"))
      (node (ref "U1") (pin "28") (pinfunction "AN13/RB13_28") (pintype "passive"))
    )
    (net (code "54") (name "/LightR_OUT") (class "Default")
      (node (ref "D10") (pin "1") (pinfunction "A_1") (pintype "passive"))
      (node (ref "J4") (pin "8") (pinfunction "8_8") (pintype "passive"))
      (node (ref "Q6") (pin "1") (pinfunction "D_1") (pintype "passive"))
    )
    (net (code "55") (name "/MCLR") (class "Default")
      (node (ref "J7") (pin "1") (pinfunction "1_1") (pintype "passive"))
      (node (ref "R2") (pin "1") (pinfunction "1_1") (pintype "passive"))
      (node (ref "U1") (pin "7") (pinfunction "~{MCLR}_7") (pintype "passive"))
    )
    (net (code "56") (name "/PGC") (class "Default")
      (node (ref "J7") (pin "5") (pinfunction "5_5") (pintype "passive"))
      (node (ref "U1") (pin "17") (pinfunction "PGC/EMUC/AN6/OCFA/RB6_17") (pintype "passive"))
    )
    (net (code "57") (name "/PGD") (class "Default")
      (node (ref "J7") (pin "4") (pinfunction "4_4") (pintype "passive"))
      (node (ref "U1") (pin "18") (pinfunction "PGD/EMUD/AN7/RB7_18") (pintype "passive"))
    )
    (net (code "58") (name "/RESET") (class "Default")
      (node (ref "C5") (pin "2") (pinfunction "2_2") (pintype "passive"))
      (node (ref "D2") (pin "1") (pinfunction "A_1") (pintype "passive"))
      (node (ref "R1") (pin "2") (pinfunction "2_2") (pintype "passive"))
      (node (ref "R2") (pin "2") (pinfunction "2_2") (pintype "passive"))
      (node (ref "U3") (pin "1") (pinfunction "~{RST}_1") (pintype "passive"))
    )
    (net (code "59") (name "/RX") (class "Default")
      (node (ref "J2") (pin "10") (pinfunction "10_10") (pintype "passive"))
      (node (ref "U1") (pin "34") (pinfunction "U1RX/SDI1/RF2_34") (pintype "passive"))
    )
    (net (code "60") (name "/TX") (class "Default")
      (node (ref "J2") (pin "8") (pinfunction "8_8") (pintype "passive"))
      (node (ref "U1") (pin "33") (pinfunction "EMUD3/U1TX/SDO1/RF3_33") (pintype "passive"))
    )
    (net (code "61") (name "/WDI") (class "Default")
      (node (ref "R9") (pin "1") (pinfunction "1_1") (pintype "passive"))
      (node (ref "U3") (pin "4") (pinfunction "WDI_4") (pintype "passive"))
    )
    (net (code "62") (name "GND") (class "Default")
      (node (ref "C1") (pin "2") (pinfunction "2_2") (pintype "passive"))
      (node (ref "C10") (pin "2") (pinfunction "2_2") (pintype "passive"))
      (node (ref "C11") (pin "2") (pinfunction "2_2") (pintype "passive"))
      (node (ref "C12") (pin "2") (pinfunction "2_2") (pintype "passive"))
      (node (ref "C13") (pin "2") (pinfunction "2_2") (pintype "passive"))
      (node (ref "C14") (pin "2") (pinfunction "2_2") (pintype "passive"))
      (node (ref "C15") (pin "2") (pinfunction "2_2") (pintype "passive"))
      (node (ref "C16") (pin "2") (pinfunction "2_2") (pintype "passive"))
      (node (ref "C17") (pin "2") (pinfunction "2_2") (pintype "passive"))
      (node (ref "C18") (pin "2") (pinfunction "2_2") (pintype "passive"))
      (node (ref "C19") (pin "2") (pinfunction "2_2") (pintype "passive"))
      (node (ref "C2") (pin "2") (pinfunction "2_2") (pintype "passive"))
      (node (ref "C20") (pin "2") (pinfunction "2_2") (pintype "passive"))
      (node (ref "C21") (pin "2") (pinfunction "2_2") (pintype "passive"))
      (node (ref "C22") (pin "2") (pinfunction "2_2") (pintype "passive"))
      (node (ref "C23") (pin "1") (pinfunction "1_1") (pintype "passive"))
      (node (ref "C24") (pin "1") (pinfunction "1_1") (pintype "passive"))
      (node (ref "C3") (pin "2") (pinfunction "2_2") (pintype "passive"))
      (node (ref "C4") (pin "2") (pinfunction "2_2") (pintype "passive"))
      (node (ref "C5") (pin "1") (pinfunction "1_1") (pintype "passive"))
      (node (ref "C6") (pin "2") (pinfunction "2_2") (pintype "passive"))
      (node (ref "C7") (pin "2") (pinfunction "2_2") (pintype "passive"))
      (node (ref "C8") (pin "1") (pinfunction "1_1") (pintype "passive"))
      (node (ref "C9") (pin "1") (pinfunction "1_1") (pintype "passive"))
      (node (ref "D11") (pin "1") (pinfunction "A_1") (pintype "passive"))
      (node (ref "D12") (pin "1") (pinfunction "A_1") (pintype "passive"))
      (node (ref "D13") (pin "1") (pinfunction "A_1") (pintype "passive"))
      (node (ref "D14") (pin "1") (pinfunction "A_1") (pintype "passive"))
      (node (ref "D4") (pin "1") (pinfunction "A_1") (pintype "passive"))
      (node (ref "D5") (pin "1") (pinfunction "A_1") (pintype "passive"))
      (node (ref "D6") (pin "1") (pinfunction "A_1") (pintype "passive"))
      (node (ref "D7") (pin "1") (pinfunction "A_1") (pintype "passive"))
      (node (ref "J1") (pin "14") (pinfunction "14_14") (pintype "passive"))
      (node (ref "J2") (pin "12") (pinfunction "12_12") (pintype "passive"))
      (node (ref "J2") (pin "14") (pinfunction "14_14") (pintype "passive"))
      (node (ref "J3") (pin "1") (pinfunction "1_1") (pintype "passive"))
      (node (ref "J4") (pin "1") (pinfunction "1_1") (pintype "passive"))
      (node (ref "J7") (pin "3") (pinfunction "3_3") (pintype "passive"))
      (node (ref "LED1") (pin "2") (pinfunction "K_2") (pintype "passive"))
      (node (ref "Q1") (pin "2") (pinfunction "S_2") (pintype "passive"))
      (node (ref "Q2") (pin "2") (pinfunction "S_2") (pintype "passive"))
      (node (ref "Q3") (pin "2") (pinfunction "S_2") (pintype "passive"))
      (node (ref "Q4") (pin "2") (pinfunction "S_2") (pintype "passive"))
      (node (ref "Q5") (pin "2") (pinfunction "S_2") (pintype "passive"))
      (node (ref "Q6") (pin "2") (pinfunction "S_2") (pintype "passive"))
      (node (ref "Q7") (pin "2") (pinfunction "S_2") (pintype "passive"))
      (node (ref "R11") (pin "2") (pinfunction "2_2") (pintype "passive"))
      (node (ref "R14") (pin "2") (pinfunction "2_2") (pintype "passive"))
      (node (ref "R15") (pin "2") (pinfunction "2_2") (pintype "passive"))
      (node (ref "R18") (pin "2") (pinfunction "2_2") (pintype "passive"))
      (node (ref "R19") (pin "2") (pinfunction "2_2") (pintype "passive"))
      (node (ref "R20") (pin "2") (pinfunction "2_2") (pintype "passive"))
      (node (ref "R26") (pin "2") (pinfunction "2_2") (pintype "passive"))
      (node (ref "R31") (pin "2") (pinfunction "2_2") (pintype "passive"))
      (node (ref "R32") (pin "2") (pinfunction "2_2") (pintype "passive"))
      (node (ref "R39") (pin "2") (pinfunction "2_2") (pintype "passive"))
      (node (ref "R40") (pin "2") (pinfunction "2_2") (pintype "passive"))
      (node (ref "R45") (pin "1") (pinfunction "1_1") (pintype "passive"))
      (node (ref "R46") (pin "1") (pinfunction "1_1") (pintype "passive"))
      (node (ref "R7") (pin "1") (pinfunction "1_1") (pintype "passive"))
      (node (ref "S1") (pin "1") (pintype "passive"))
      (node (ref "U1") (pin "20") (pinfunction "AVSS_20") (pintype "passive"))
      (node (ref "U1") (pin "25") (pinfunction "VSS_25") (pintype "passive"))
      (node (ref "U1") (pin "41") (pinfunction "VSS_41") (pintype "passive"))
      (node (ref "U1") (pin "56") (pinfunction "VSS_56") (pintype "passive"))
      (node (ref "U1") (pin "9") (pinfunction "VSS_9") (pintype "passive"))
      (node (ref "U2") (pin "4") (pinfunction "GND_4") (pintype "power_in"))
      (node (ref "U3") (pin "2") (pinfunction "Vss_2") (pintype "passive"))
      (node (ref "U4") (pin "2") (pinfunction "GND_2") (pintype "power_in"))
      (node (ref "U5") (pin "2") (pinfunction "GND_2") (pintype "power_in"))
    )
    (net (code "63") (name "Net-(C23-Pad2)") (class "Default")
      (node (ref "C23") (pin "2") (pinfunction "2_2") (pintype "passive"))
      (node (ref "R33") (pin "2") (pinfunction "2_2") (pintype "passive"))
      (node (ref "R41") (pin "2") (pinfunction "2_2") (pintype "passive"))
      (node (ref "R43") (pin "2") (pinfunction "2_2") (pintype "passive"))
    )
    (net (code "64") (name "Net-(C24-Pad2)") (class "Default")
      (node (ref "C24") (pin "2") (pinfunction "2_2") (pintype "passive"))
      (node (ref "R34") (pin "2") (pinfunction "2_2") (pintype "passive"))
      (node (ref "R42") (pin "2") (pinfunction "2_2") (pintype "passive"))
      (node (ref "R44") (pin "2") (pinfunction "2_2") (pintype "passive"))
    )
    (net (code "65") (name "Net-(D3-A)") (class "Default")
      (node (ref "C8") (pin "2") (pinfunction "2_2") (pintype "passive"))
      (node (ref "D3") (pin "1") (pinfunction "A_1") (pintype "passive"))
      (node (ref "R5") (pin "1") (pinfunction "1_1") (pintype "passive"))
      (node (ref "S1") (pin "2") (pintype "passive"))
      (node (ref "U3") (pin "3") (pinfunction "~{MR}_3") (pintype "passive"))
    )
    (net (code "66") (name "Net-(D4-K)") (class "Default")
      (node (ref "D4") (pin "2") (pinfunction "K_2") (pintype "passive"))
      (node (ref "L1") (pin "1") (pinfunction "1_1") (pintype "passive"))
      (node (ref "U2") (pin "2") (pinfunction "SWE_2") (pintype "open_emitter"))
    )
    (net (code "67") (name "Net-(D8-K)") (class "Default")
      (node (ref "D8") (pin "2") (pinfunction "K_2") (pintype "passive"))
      (node (ref "R21") (pin "2") (pinfunction "2_2") (pintype "passive"))
    )
    (net (code "68") (name "Net-(D9-K)") (class "Default")
      (node (ref "D9") (pin "2") (pinfunction "K_2") (pintype "passive"))
      (node (ref "R22") (pin "2") (pinfunction "2_2") (pintype "passive"))
    )
    (net (code "69") (name "Net-(D10-K)") (class "Default")
      (node (ref "D10") (pin "2") (pinfunction "K_2") (pintype "passive"))
      (node (ref "R23") (pin "2") (pinfunction "2_2") (pintype "passive"))
    )
    (net (code "70") (name "Net-(LED1-A)") (class "Default")
      (node (ref "LED1") (pin "1") (pinfunction "A_1") (pintype "passive"))
      (node (ref "R4") (pin "2") (pinfunction "2_2") (pintype "passive"))
    )
    (net (code "71") (name "Net-(LED2-K)") (class "Default")
      (node (ref "LED2") (pin "2") (pinfunction "K_2") (pintype "passive"))
      (node (ref "R10") (pin "1") (pinfunction "1_1") (pintype "passive"))
    )
    (net (code "72") (name "Net-(LED3-K)") (class "Default")
      (node (ref "LED3") (pin "2") (pinfunction "K_2") (pintype "passive"))
      (node (ref "R11") (pin "1") (pinfunction "1_1") (pintype "passive"))
    )
    (net (code "73") (name "Net-(LED4-K)") (class "Default")
      (node (ref "LED4") (pin "2") (pinfunction "K_2") (pintype "passive"))
      (node (ref "R16") (pin "1") (pinfunction "1_1") (pintype "passive"))
    )
    (net (code "74") (name "Net-(LED5-K)") (class "Default")
      (node (ref "LED5") (pin "2") (pinfunction "K_2") (pintype "passive"))
      (node (ref "R17") (pin "1") (pinfunction "1_1") (pintype "passive"))
    )
    (net (code "75") (name "Net-(Q1-G)") (class "Default")
      (node (ref "Q1") (pin "3") (pinfunction "G_3") (pintype "passive"))
      (node (ref "R3") (pin "2") (pinfunction "2_2") (pintype "passive"))
    )
    (net (code "76") (name "Net-(Q3-D)") (class "Default")
      (node (ref "Q3") (pin "1") (pinfunction "D_1") (pintype "passive"))
      (node (ref "R21") (pin "1") (pinfunction "1_1") (pintype "passive"))
      (node (ref "R22") (pin "1") (pinfunction "1_1") (pintype "passive"))
      (node (ref "R23") (pin "1") (pinfunction "1_1") (pintype "passive"))
    )
    (net (code "77") (name "Net-(U1-OSC1{slash}CLKI)") (class "Default")
      (node (ref "C10") (pin "1") (pinfunction "1_1") (pintype "passive"))
      (node (ref "U1") (pin "39") (pinfunction "OSC1/CLKI_39") (pintype "passive"))
      (node (ref "Y1") (pin "2") (pinfunction "OSC2_2") (pintype "passive"))
    )
    (net (code "78") (name "Net-(U1-OSC2{slash}CLKO{slash}RC15)") (class "Default")
      (node (ref "C11") (pin "1") (pinfunction "1_1") (pintype "passive"))
      (node (ref "U1") (pin "40") (pinfunction "OSC2/CLKO/RC15_40") (pintype "passive"))
      (node (ref "Y1") (pin "1") (pinfunction "OSC1_1") (pintype "passive"))
    )
    (net (code "79") (name "Net-(U1-SCL{slash}RG2)") (class "Default")
      (node (ref "R10") (pin "2") (pinfunction "2_2") (pintype "passive"))
      (node (ref "U1") (pin "37") (pinfunction "SCL/RG2_37") (pintype "passive"))
    )
    (net (code "80") (name "Net-(U1-~{SS2}{slash}CN11{slash}RG9)") (class "Default")
      (node (ref "R9") (pin "2") (pinfunction "2_2") (pintype "passive"))
      (node (ref "U1") (pin "8") (pinfunction "~{SS2}/CN11/RG9_8") (pintype "passive"))
    )
    (net (code "81") (name "Net-(U2--VIN)") (class "Default")
      (node (ref "R6") (pin "2") (pinfunction "2_2") (pintype "passive"))
      (node (ref "R7") (pin "2") (pinfunction "2_2") (pintype "passive"))
      (node (ref "U2") (pin "5") (pinfunction "-VIN_5") (pintype "input"))
    )
    (net (code "82") (name "Net-(U2-DRVC)") (class "Default")
      (node (ref "R8") (pin "1") (pinfunction "1_1") (pintype "passive"))
      (node (ref "U2") (pin "1") (pinfunction "SWC_1") (pintype "open_collector"))
      (node (ref "U2") (pin "7") (pinfunction "IPK_7") (pintype "passive"))
      (node (ref "U2") (pin "8") (pinfunction "DRVC_8") (pintype "open_collector"))
    )
    (net (code "83") (name "Net-(U2-TCAP)") (class "Default")
      (node (ref "C9") (pin "2") (pinfunction "2_2") (pintype "passive"))
      (node (ref "U2") (pin "3") (pinfunction "TCAP_3") (pintype "passive"))
    )
    (net (code "84") (name "Net-(U4-RS)") (class "Default")
      (node (ref "R31") (pin "1") (pinfunction "1_1") (pintype "passive"))
      (node (ref "U4") (pin "8") (pinfunction "RS_8") (pintype "passive"))
    )
    (net (code "85") (name "Net-(U4-VREF)") (class "Default")
      (node (ref "R33") (pin "1") (pinfunction "1_1") (pintype "passive"))
      (node (ref "U4") (pin "5") (pinfunction "VREF_5") (pintype "output"))
    )
    (net (code "86") (name "Net-(U5-RS)") (class "Default")
      (node (ref "R32") (pin "1") (pinfunction "1_1") (pintype "passive"))
      (node (ref "U5") (pin "8") (pinfunction "RS_8") (pintype "passive"))
    )
    (net (code "87") (name "Net-(U5-VREF)") (class "Default")
      (node (ref "R34") (pin "1") (pinfunction "1_1") (pintype "passive"))
      (node (ref "U5") (pin "5") (pinfunction "VREF_5") (pintype "output"))
    )
    (net (code "88") (name "unconnected-(U1-COFS{slash}RG15-Pad1)") (class "Default")
      (node (ref "U1") (pin "1") (pinfunction "COFS/RG15_1") (pintype "passive"))
    )
    (net (code "89") (name "unconnected-(U1-CSCK{slash}RG14-Pad62)") (class "Default")
      (node (ref "U1") (pin "62") (pinfunction "CSCK/RG14_62") (pintype "passive"))
    )
    (net (code "90") (name "unconnected-(U1-CSDI{slash}RG12-Pad63)") (class "Default")
      (node (ref "U1") (pin "63") (pinfunction "CSDI/RG12_63") (pintype "passive"))
    )
    (net (code "91") (name "unconnected-(U1-CSDO{slash}RG13-Pad64)") (class "Default")
      (node (ref "U1") (pin "64") (pinfunction "CSDO/RG13_64") (pintype "passive"))
    )
    (net (code "92") (name "unconnected-(U1-EMUC3{slash}SCK1{slash}INT0{slash}RF6-Pad35)") (class "Default")
      (node (ref "U1") (pin "35") (pinfunction "EMUC3/SCK1/INT0/RF6_35") (pintype "passive"))
    )
    (net (code "93") (name "unconnected-(U1-SCK2{slash}CN8{slash}RG6-Pad4)") (class "Default")
      (node (ref "U1") (pin "4") (pinfunction "SCK2/CN8/RG6_4") (pintype "passive"))
    )
    (net (code "94") (name "unconnected-(U1-SDA{slash}RG3-Pad36)") (class "Default")
      (node (ref "U1") (pin "36") (pinfunction "SDA/RG3_36") (pintype "passive"))
    )
    (net (code "95") (name "unconnected-(U1-SDI2{slash}CN9{slash}RG7-Pad5)") (class "Default")
      (node (ref "U1") (pin "5") (pinfunction "SDI2/CN9/RG7_5") (pintype "passive"))
    )
    (net (code "96") (name "unconnected-(U1-SDO2{slash}CN10{slash}RG8-Pad6)") (class "Default")
      (node (ref "U1") (pin "6") (pinfunction "SDO2/CN10/RG8_6") (pintype "passive"))
    )
    (net (code "97") (name "unconnected-(U1-T2CK{slash}RC1-Pad2)") (class "Default")
      (node (ref "U1") (pin "2") (pinfunction "T2CK/RC1_2") (pintype "passive"))
    )
    (net (code "98") (name "unconnected-(U1-T3CK{slash}RC2-Pad3)") (class "Default")
      (node (ref "U1") (pin "3") (pinfunction "T3CK/RC2_3") (pintype "passive"))
    )
  )
)
